# SCH_L298N_shame_2022-05-20.net
KiCad netlist of a schematic drawn in EasyEDA
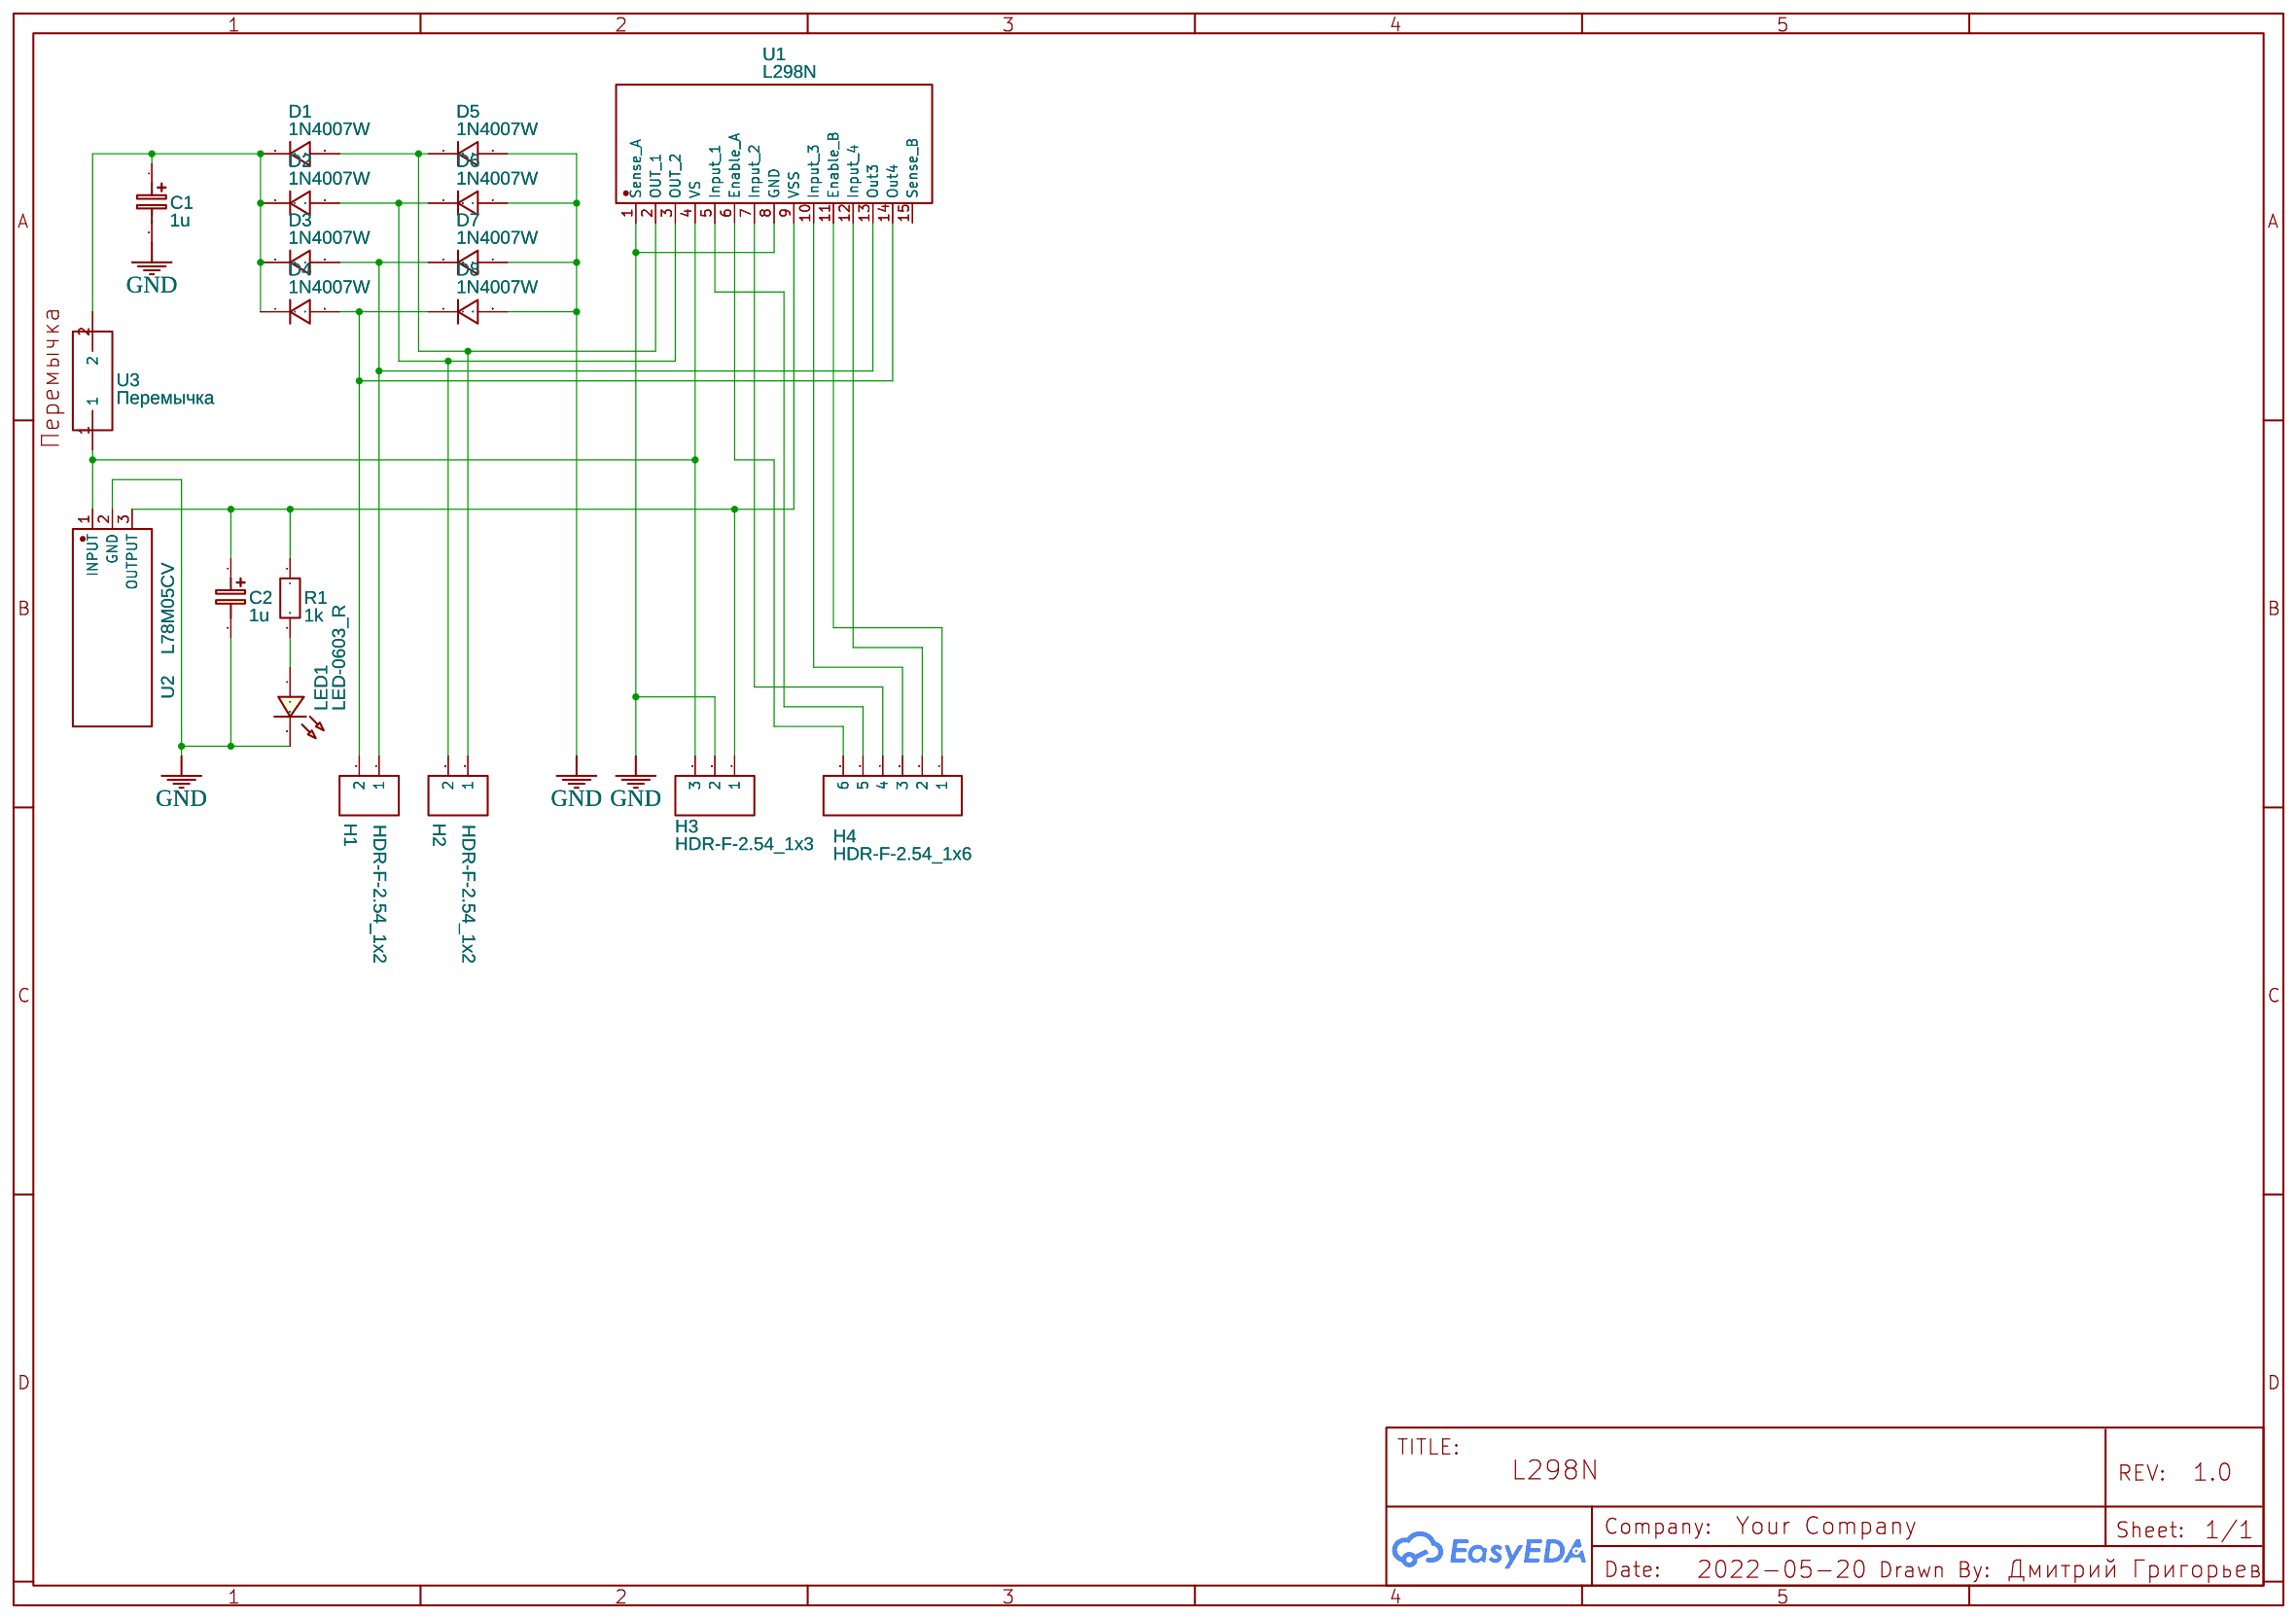
[diagram p0: schematic sheet]

(export (version "E")
  (design (tool "Eeschema 10.0.6"))
  (components
    (comp (ref "C1") (value "1u") (libsource (lib "") (part "C_Tan_SMD_A_EU_1")))
    (comp (ref "C2") (value "1u") (libsource (lib "") (part "C_Tan_SMD_A_EU")))
    (comp (ref "D1")
      (value "1N4007W")
      (fields (field (name "BOM_Supplier Part") "C328592"))
      (libsource (lib "") (part "1N4007W"))
    )
    (comp (ref "D2")
      (value "1N4007W")
      (fields (field (name "BOM_Supplier Part") "C328592"))
      (libsource (lib "") (part "1N4007W"))
    )
    (comp (ref "D3")
      (value "1N4007W")
      (fields (field (name "BOM_Supplier Part") "C328592"))
      (libsource (lib "") (part "1N4007W"))
    )
    (comp (ref "D4")
      (value "1N4007W")
      (fields (field (name "BOM_Supplier Part") "C328592"))
      (libsource (lib "") (part "1N4007W"))
    )
    (comp (ref "D5")
      (value "1N4007W")
      (fields (field (name "BOM_Supplier Part") "C328592"))
      (libsource (lib "") (part "1N4007W"))
    )
    (comp (ref "D6")
      (value "1N4007W")
      (fields (field (name "BOM_Supplier Part") "C328592"))
      (libsource (lib "") (part "1N4007W"))
    )
    (comp (ref "D7")
      (value "1N4007W")
      (fields (field (name "BOM_Supplier Part") "C328592"))
      (libsource (lib "") (part "1N4007W"))
    )
    (comp (ref "D8")
      (value "1N4007W")
      (fields (field (name "BOM_Supplier Part") "C328592"))
      (libsource (lib "") (part "1N4007W"))
    )
    (comp (ref "H1")
      (value "HDR-F-2.54_1x2")
      (fields (field (name "BOM_Supplier Part") "C49661"))
      (libsource (lib "") (part "HDR-F-2.54_1x2"))
    )
    (comp (ref "H2")
      (value "HDR-F-2.54_1x2")
      (fields (field (name "BOM_Supplier Part") "C49661"))
      (libsource (lib "") (part "HDR-F-2.54_1x2"))
    )
    (comp (ref "H3")
      (value "HDR-F-2.54_1x3")
      (fields (field (name "BOM_Supplier Part") "C146690"))
      (libsource (lib "") (part "HDR-F-2.54_1x3"))
    )
    (comp (ref "H4")
      (value "HDR-F-2.54_1x6")
      (fields (field (name "BOM_Supplier Part") "C40877"))
      (libsource (lib "") (part "HDR-F-2.54_1x6"))
    )
    (comp (ref "LED1")
      (value "LED-0603_R")
      (fields
        (field (name "BOM_Manufacturer Part") "19-217/R6C-AL1M2VY/3T")
        (field (name "BOM_Supplier Part") "C72044")
      )
      (libsource (lib "") (part "LED-0603_R"))
    )
    (comp (ref "R1") (value "1k") (libsource (lib "") (part "R_0603_EU")))
    (comp (ref "U1")
      (value "L298N")
      (fields (field (name "BOM_Supplier Part") "C434589"))
      (libsource (lib "") (part "L298N"))
    )
    (comp (ref "U2")
      (value "L78M05CV")
      (fields (field (name "BOM_Supplier Part") "C283462"))
      (libsource (lib "") (part "L78M05CV"))
    )
    (comp (ref "U3")
      (value "Перемычка")
      (fields (field (name "BOM_Manufacturer Part") "New SchematicLib"))
      (libsource (lib "") (part "Перемычка"))
    )
  )
  (nets
    (net (code "1") (name "GND") (class "Default")
      (node (ref "C1") (pin "2") (pinfunction "2_2") (pintype "unspecified"))
      (node (ref "C2") (pin "2") (pinfunction "2_2") (pintype "unspecified"))
      (node (ref "D5") (pin "2") (pinfunction "2_2") (pintype "unspecified"))
      (node (ref "D6") (pin "2") (pinfunction "2_2") (pintype "unspecified"))
      (node (ref "D7") (pin "2") (pinfunction "2_2") (pintype "unspecified"))
      (node (ref "D8") (pin "2") (pinfunction "2_2") (pintype "unspecified"))
      (node (ref "H3") (pin "2") (pinfunction "2_2") (pintype "input"))
      (node (ref "LED1") (pin "2") (pinfunction "2_2") (pintype "unspecified"))
      (node (ref "U1") (pin "1") (pinfunction "Sense_A_1") (pintype "unspecified"))
      (node (ref "U1") (pin "8") (pinfunction "GND_8") (pintype "unspecified"))
      (node (ref "U2") (pin "2") (pinfunction "GND_2") (pintype "unspecified"))
    )
    (net (code "2") (name "Net-(C1-Pad1)") (class "Default")
      (node (ref "C1") (pin "1") (pinfunction "1_1") (pintype "unspecified"))
      (node (ref "D1") (pin "1") (pinfunction "1_1") (pintype "unspecified"))
      (node (ref "D2") (pin "1") (pinfunction "1_1") (pintype "unspecified"))
      (node (ref "D3") (pin "1") (pinfunction "1_1") (pintype "unspecified"))
      (node (ref "D4") (pin "1") (pinfunction "1_1") (pintype "unspecified"))
      (node (ref "U3") (pin "2") (pinfunction "2_2") (pintype "unspecified"))
    )
    (net (code "3") (name "Net-(LED1-Pad1)") (class "Default")
      (node (ref "LED1") (pin "1") (pinfunction "1_1") (pintype "unspecified"))
      (node (ref "R1") (pin "2") (pinfunction "2_2") (pintype "unspecified"))
    )
    (net (code "4") (name "Net-(U1-Enable_A)") (class "Default")
      (node (ref "H4") (pin "6") (pinfunction "6_6") (pintype "input"))
      (node (ref "U1") (pin "6") (pinfunction "Enable_A_6") (pintype "unspecified"))
    )
    (net (code "5") (name "Net-(U1-Enable_B)") (class "Default")
      (node (ref "H4") (pin "1") (pinfunction "1_1") (pintype "input"))
      (node (ref "U1") (pin "11") (pinfunction "Enable_B_11") (pintype "unspecified"))
    )
    (net (code "6") (name "Net-(U1-Input_1)") (class "Default")
      (node (ref "H4") (pin "5") (pinfunction "5_5") (pintype "input"))
      (node (ref "U1") (pin "5") (pinfunction "Input_1_5") (pintype "unspecified"))
    )
    (net (code "7") (name "Net-(U1-Input_2)") (class "Default")
      (node (ref "H4") (pin "4") (pinfunction "4_4") (pintype "input"))
      (node (ref "U1") (pin "7") (pinfunction "Input_2_7") (pintype "unspecified"))
    )
    (net (code "8") (name "Net-(U1-Input_3)") (class "Default")
      (node (ref "H4") (pin "3") (pinfunction "3_3") (pintype "input"))
      (node (ref "U1") (pin "10") (pinfunction "Input_3_10") (pintype "unspecified"))
    )
    (net (code "9") (name "Net-(U1-Input_4)") (class "Default")
      (node (ref "H4") (pin "2") (pinfunction "2_2") (pintype "input"))
      (node (ref "U1") (pin "12") (pinfunction "Input_4_12") (pintype "unspecified"))
    )
    (net (code "10") (name "Net-(U1-OUT_1)") (class "Default")
      (node (ref "D1") (pin "2") (pinfunction "2_2") (pintype "unspecified"))
      (node (ref "D5") (pin "1") (pinfunction "1_1") (pintype "unspecified"))
      (node (ref "H2") (pin "1") (pinfunction "1_1") (pintype "input"))
      (node (ref "U1") (pin "2") (pinfunction "OUT_1_2") (pintype "unspecified"))
    )
    (net (code "11") (name "Net-(U1-OUT_2)") (class "Default")
      (node (ref "D2") (pin "2") (pinfunction "2_2") (pintype "unspecified"))
      (node (ref "D6") (pin "1") (pinfunction "1_1") (pintype "unspecified"))
      (node (ref "H2") (pin "2") (pinfunction "2_2") (pintype "input"))
      (node (ref "U1") (pin "3") (pinfunction "OUT_2_3") (pintype "unspecified"))
    )
    (net (code "12") (name "Net-(U1-Out3)") (class "Default")
      (node (ref "D3") (pin "2") (pinfunction "2_2") (pintype "unspecified"))
      (node (ref "D7") (pin "1") (pinfunction "1_1") (pintype "unspecified"))
      (node (ref "H1") (pin "1") (pinfunction "1_1") (pintype "input"))
      (node (ref "U1") (pin "13") (pinfunction "Out3_13") (pintype "unspecified"))
    )
    (net (code "13") (name "Net-(U1-Out4)") (class "Default")
      (node (ref "D4") (pin "2") (pinfunction "2_2") (pintype "unspecified"))
      (node (ref "D8") (pin "1") (pinfunction "1_1") (pintype "unspecified"))
      (node (ref "H1") (pin "2") (pinfunction "2_2") (pintype "input"))
      (node (ref "U1") (pin "14") (pinfunction "Out4_14") (pintype "unspecified"))
    )
    (net (code "14") (name "Net-(U1-VS)") (class "Default")
      (node (ref "H3") (pin "3") (pinfunction "3_3") (pintype "input"))
      (node (ref "U1") (pin "4") (pinfunction "VS_4") (pintype "unspecified"))
      (node (ref "U2") (pin "1") (pinfunction "INPUT_1") (pintype "unspecified"))
      (node (ref "U3") (pin "1") (pinfunction "1_1") (pintype "unspecified"))
    )
    (net (code "15") (name "Net-(U1-VSS)") (class "Default")
      (node (ref "C2") (pin "1") (pinfunction "1_1") (pintype "unspecified"))
      (node (ref "H3") (pin "1") (pinfunction "1_1") (pintype "input"))
      (node (ref "R1") (pin "1") (pinfunction "1_1") (pintype "unspecified"))
      (node (ref "U1") (pin "9") (pinfunction "VSS_9") (pintype "unspecified"))
      (node (ref "U2") (pin "3") (pinfunction "OUTPUT_3") (pintype "unspecified"))
    )
    (net (code "16") (name "unconnected-(U1-Sense_B-Pad15)") (class "Default")
      (node (ref "U1") (pin "15") (pinfunction "Sense_B_15") (pintype "unspecified"))
    )
  )
)
